# Sensor_Board_2_01_HX711_DS18b2.net
KiCad netlist of a schematic drawn in EAGLE
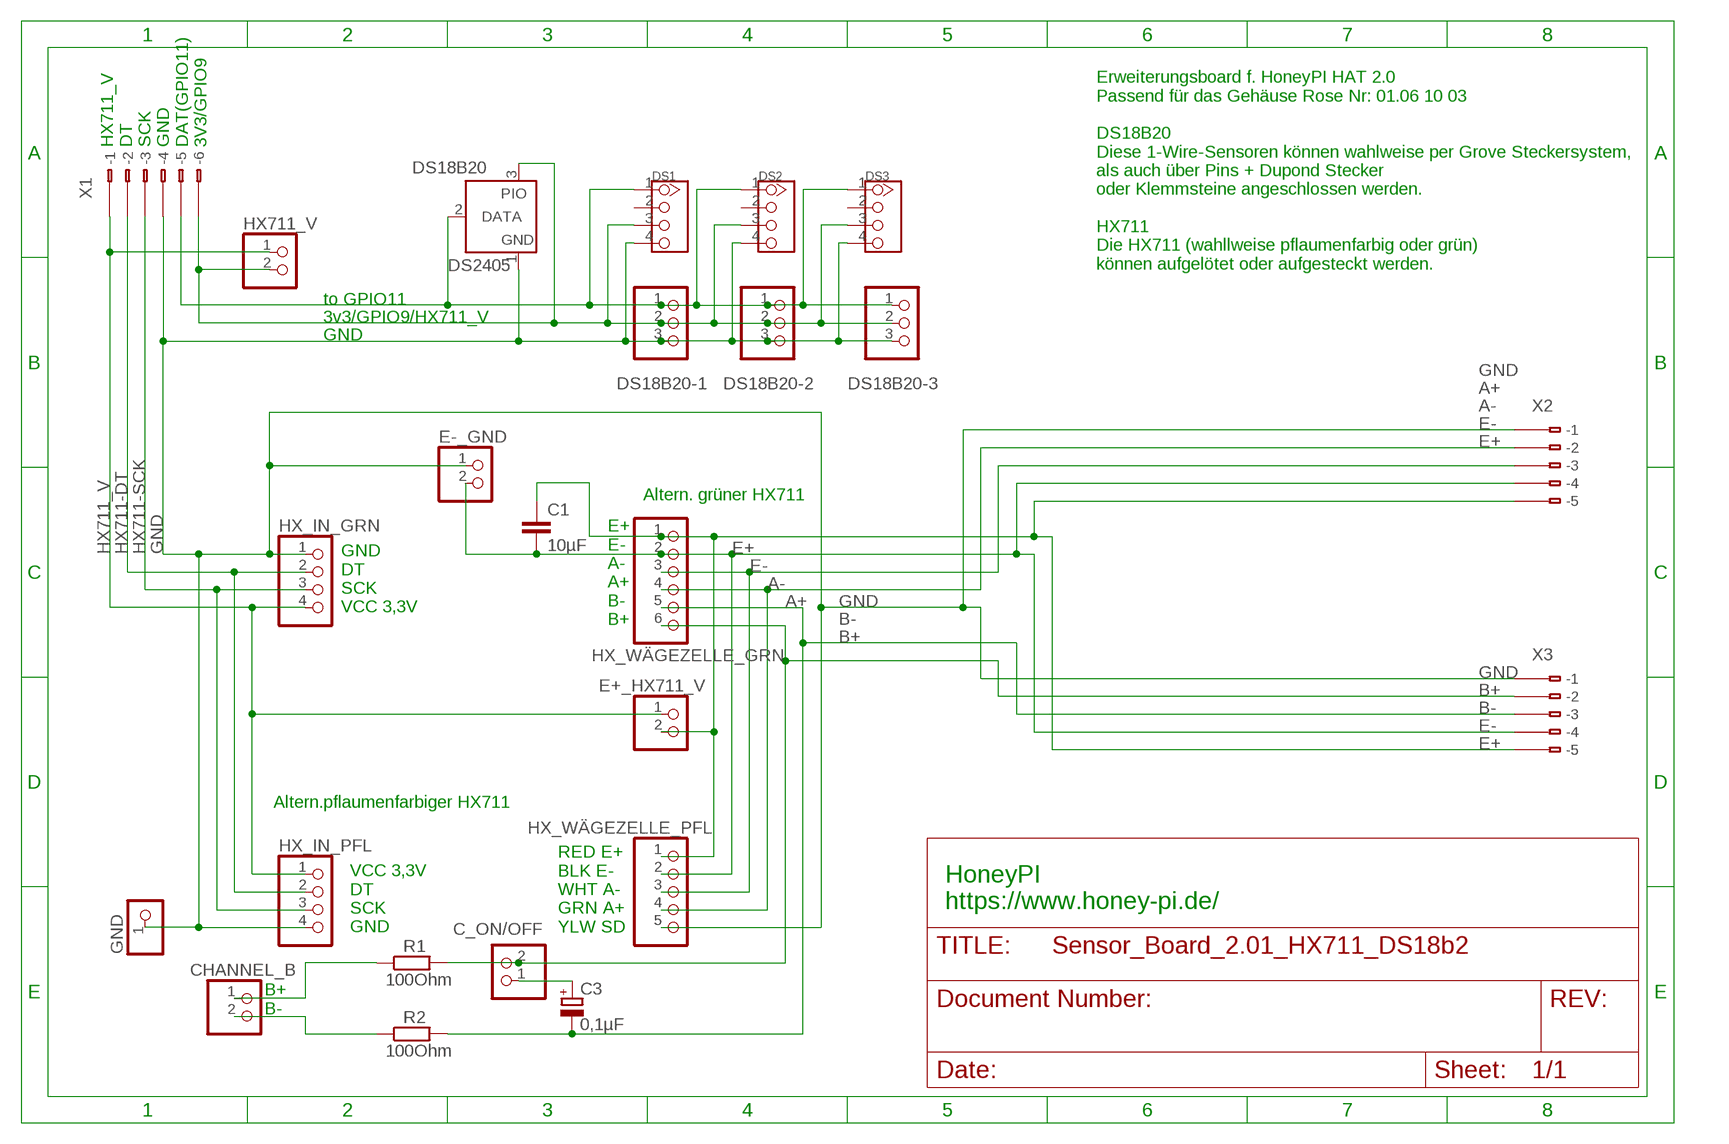
[diagram p0: schematic, sheet 1]

(export (version "E")
  (design (tool "Eeschema 10.0.6"))
  (components
    (comp (ref "C1")
      (value "10µF")
      (footprint "eagle-import:C5B2.5")
      (libsource (lib "eagle-import") (part "C5/2.5"))
    )
    (comp (ref "C3")
      (value "0,1µF")
      (footprint "eagle-import:E2,5-7")
      (libsource (lib "eagle-import") (part "CPOL-EUE2.5-7"))
    )
    (comp (ref "CHANNEL_B")
      (value "PINHD-1X2")
      (footprint "eagle-import:1X02")
      (libsource (lib "eagle-import") (part "PINHD-1X2"))
    )
    (comp (ref "C_ON/OFF")
      (value "PINHD-1X2")
      (footprint "eagle-import:1X02")
      (libsource (lib "eagle-import") (part "PINHD-1X2"))
    )
    (comp (ref "DS1")
      (value "TWIG-4P-2.0-2.0")
      (footprint "eagle-import:4P-2.0")
      (libsource (lib "eagle-import") (part "TWIG-4P-2.0-2.0"))
    )
    (comp (ref "DS2")
      (value "TWIG-4P-2.0-2.0")
      (footprint "eagle-import:4P-2.0")
      (libsource (lib "eagle-import") (part "TWIG-4P-2.0-2.0"))
    )
    (comp (ref "DS3")
      (value "TWIG-4P-2.0-2.0")
      (footprint "eagle-import:4P-2.0")
      (libsource (lib "eagle-import") (part "TWIG-4P-2.0-2.0"))
    )
    (comp (ref "DS18B20")
      (value "DS2405")
      (footprint "eagle-import:TO92-")
      (fields (field (name "MF") "DALLAS SEMICONDUCTOR"))
      (libsource (lib "eagle-import") (part "DS2405"))
    )
    (comp (ref "DS18B20-1")
      (value "PINHD-1X3")
      (footprint "eagle-import:1X03")
      (libsource (lib "eagle-import") (part "PINHD-1X3"))
    )
    (comp (ref "DS18B20-2")
      (value "PINHD-1X3")
      (footprint "eagle-import:1X03")
      (libsource (lib "eagle-import") (part "PINHD-1X3"))
    )
    (comp (ref "DS18B20-3")
      (value "PINHD-1X3")
      (footprint "eagle-import:1X03")
      (libsource (lib "eagle-import") (part "PINHD-1X3"))
    )
    (comp (ref "E+_HX711_V")
      (value "PINHD-1X2")
      (footprint "eagle-import:1X02")
      (libsource (lib "eagle-import") (part "PINHD-1X2"))
    )
    (comp (ref "E-_GND")
      (value "PINHD-1X2")
      (footprint "eagle-import:1X02")
      (libsource (lib "eagle-import") (part "PINHD-1X2"))
    )
    (comp (ref "GND")
      (value "PINHD-1X1")
      (footprint "eagle-import:1X01")
      (libsource (lib "eagle-import") (part "PINHD-1X1"))
    )
    (comp (ref "HX711_V")
      (value "PINHD-1X2")
      (footprint "eagle-import:1X02")
      (libsource (lib "eagle-import") (part "PINHD-1X2"))
    )
    (comp (ref "HX_IN_GRN")
      (value "PINHD-1X4")
      (footprint "eagle-import:1X04")
      (libsource (lib "eagle-import") (part "PINHD-1X4"))
    )
    (comp (ref "HX_IN_PFL")
      (value "PINHD-1X4")
      (footprint "eagle-import:1X04")
      (libsource (lib "eagle-import") (part "PINHD-1X4"))
    )
    (comp (ref "HX_WÄGEZELLE_GRN")
      (value "PINHD-1X6")
      (footprint "eagle-import:1X06")
      (libsource (lib "eagle-import") (part "PINHD-1X6"))
    )
    (comp (ref "HX_WÄGEZELLE_PFL")
      (value "PINHD-1X5")
      (footprint "eagle-import:1X05")
      (libsource (lib "eagle-import") (part "PINHD-1X5"))
    )
    (comp (ref "R1")
      (value "100Ohm")
      (footprint "eagle-import:0207_10")
      (libsource (lib "eagle-import") (part "R-EU_0207/10"))
    )
    (comp (ref "R2")
      (value "100Ohm")
      (footprint "eagle-import:0207_10")
      (libsource (lib "eagle-import") (part "R-EU_0207/10"))
    )
    (comp (ref "X1")
      (value "233-506")
      (footprint "eagle-import:233-506")
      (fields (field (name "MF") "Wago Corporation") (field (name "MPN") "0233-0506"))
      (libsource (lib "eagle-import") (part "233-506"))
    )
    (comp (ref "X2")
      (value "233-505")
      (footprint "eagle-import:233-505")
      (fields (field (name "MF") "Wago Corporation") (field (name "MPN") "0233-0505"))
      (libsource (lib "eagle-import") (part "233-505"))
    )
    (comp (ref "X3")
      (value "233-505")
      (footprint "eagle-import:233-505")
      (fields (field (name "MF") "Wago Corporation") (field (name "MPN") "0233-0505"))
      (libsource (lib "eagle-import") (part "233-505"))
    )
  )
  (nets
    (net (code "1") (name "/A+") (class "Default")
      (node (ref "HX_WÄGEZELLE_GRN") (pin "4") (pinfunction "4_4") (pintype "passive"))
      (node (ref "HX_WÄGEZELLE_PFL") (pin "4") (pinfunction "4_4") (pintype "passive"))
      (node (ref "X2") (pin "B2") (pinfunction "B-2_B2") (pintype "passive"))
    )
    (net (code "2") (name "/A-") (class "Default")
      (node (ref "HX_WÄGEZELLE_GRN") (pin "3") (pinfunction "3_3") (pintype "passive"))
      (node (ref "HX_WÄGEZELLE_PFL") (pin "3") (pinfunction "3_3") (pintype "passive"))
      (node (ref "X2") (pin "B3") (pinfunction "B-3_B3") (pintype "passive"))
    )
    (net (code "3") (name "/B+") (class "Default")
      (node (ref "C_ON/OFF") (pin "2") (pinfunction "2_2") (pintype "passive"))
      (node (ref "HX_WÄGEZELLE_GRN") (pin "6") (pinfunction "6_6") (pintype "passive"))
      (node (ref "R1") (pin "2") (pinfunction "2_2") (pintype "passive"))
      (node (ref "X3") (pin "B2") (pinfunction "B-2_B2") (pintype "passive"))
    )
    (net (code "4") (name "/B-") (class "Default")
      (node (ref "C3") (pin "-") (pinfunction "-_-") (pintype "passive"))
      (node (ref "HX_WÄGEZELLE_GRN") (pin "5") (pinfunction "5_5") (pintype "passive"))
      (node (ref "R2") (pin "2") (pinfunction "2_2") (pintype "passive"))
      (node (ref "X3") (pin "B3") (pinfunction "B-3_B3") (pintype "passive"))
    )
    (net (code "5") (name "/E+") (class "Default")
      (node (ref "C1") (pin "1") (pinfunction "1_1") (pintype "passive"))
      (node (ref "E+_HX711_V") (pin "2") (pinfunction "2_2") (pintype "passive"))
      (node (ref "HX_WÄGEZELLE_GRN") (pin "1") (pinfunction "1_1") (pintype "passive"))
      (node (ref "HX_WÄGEZELLE_PFL") (pin "1") (pinfunction "1_1") (pintype "passive"))
      (node (ref "X2") (pin "B5") (pinfunction "B-5_B5") (pintype "passive"))
      (node (ref "X3") (pin "B5") (pinfunction "B-5_B5") (pintype "passive"))
    )
    (net (code "6") (name "/E-") (class "Default")
      (node (ref "C1") (pin "2") (pinfunction "2_2") (pintype "passive"))
      (node (ref "E-_GND") (pin "2") (pinfunction "2_2") (pintype "passive"))
      (node (ref "HX_WÄGEZELLE_GRN") (pin "2") (pinfunction "2_2") (pintype "passive"))
      (node (ref "HX_WÄGEZELLE_PFL") (pin "2") (pinfunction "2_2") (pintype "passive"))
      (node (ref "X2") (pin "B4") (pinfunction "B-4_B4") (pintype "passive"))
      (node (ref "X3") (pin "B4") (pinfunction "B-4_B4") (pintype "passive"))
    )
    (net (code "7") (name "/GND") (class "Default")
      (node (ref "DS1") (pin "4") (pinfunction "4_4") (pintype "bidirectional"))
      (node (ref "DS18B20") (pin "1") (pinfunction "GND_1") (pintype "passive"))
      (node (ref "DS18B20-1") (pin "3") (pinfunction "3_3") (pintype "passive"))
      (node (ref "DS18B20-2") (pin "3") (pinfunction "3_3") (pintype "passive"))
      (node (ref "DS18B20-3") (pin "3") (pinfunction "3_3") (pintype "passive"))
      (node (ref "DS2") (pin "4") (pinfunction "4_4") (pintype "bidirectional"))
      (node (ref "DS3") (pin "4") (pinfunction "4_4") (pintype "bidirectional"))
      (node (ref "E-_GND") (pin "1") (pinfunction "1_1") (pintype "passive"))
      (node (ref "GND") (pin "1") (pinfunction "1_1") (pintype "passive"))
      (node (ref "HX_IN_GRN") (pin "1") (pinfunction "1_1") (pintype "passive"))
      (node (ref "HX_IN_PFL") (pin "4") (pinfunction "4_4") (pintype "passive"))
      (node (ref "HX_WÄGEZELLE_PFL") (pin "5") (pinfunction "5_5") (pintype "passive"))
      (node (ref "X1") (pin "B4") (pinfunction "B-4_B4") (pintype "passive"))
      (node (ref "X2") (pin "B1") (pinfunction "B-1_B1") (pintype "passive"))
      (node (ref "X3") (pin "B1") (pinfunction "B-1_B1") (pintype "passive"))
    )
    (net (code "8") (name "/HX711-DT") (class "Default")
      (node (ref "HX_IN_GRN") (pin "2") (pinfunction "2_2") (pintype "passive"))
      (node (ref "HX_IN_PFL") (pin "2") (pinfunction "2_2") (pintype "passive"))
      (node (ref "X1") (pin "B2") (pinfunction "B-2_B2") (pintype "passive"))
    )
    (net (code "9") (name "/HX711-SCK") (class "Default")
      (node (ref "HX_IN_GRN") (pin "3") (pinfunction "3_3") (pintype "passive"))
      (node (ref "HX_IN_PFL") (pin "3") (pinfunction "3_3") (pintype "passive"))
      (node (ref "X1") (pin "B3") (pinfunction "B-3_B3") (pintype "passive"))
    )
    (net (code "10") (name "/HX711_V") (class "Default")
      (node (ref "E+_HX711_V") (pin "1") (pinfunction "1_1") (pintype "passive"))
      (node (ref "HX711_V") (pin "1") (pinfunction "1_1") (pintype "passive"))
      (node (ref "HX_IN_GRN") (pin "4") (pinfunction "4_4") (pintype "passive"))
      (node (ref "HX_IN_PFL") (pin "1") (pinfunction "1_1") (pintype "passive"))
      (node (ref "X1") (pin "B1") (pinfunction "B-1_B1") (pintype "passive"))
    )
    (net (code "11") (name "Net-(C3-Pad+)") (class "Default")
      (node (ref "C3") (pin "+") (pinfunction "+_+") (pintype "passive"))
      (node (ref "C_ON/OFF") (pin "1") (pinfunction "1_1") (pintype "passive"))
    )
    (net (code "12") (name "Net-(CHANNEL_B-Pad1)") (class "Default")
      (node (ref "CHANNEL_B") (pin "1") (pinfunction "1_1") (pintype "passive"))
      (node (ref "R1") (pin "1") (pinfunction "1_1") (pintype "passive"))
    )
    (net (code "13") (name "Net-(CHANNEL_B-Pad2)") (class "Default")
      (node (ref "CHANNEL_B") (pin "2") (pinfunction "2_2") (pintype "passive"))
      (node (ref "R2") (pin "1") (pinfunction "1_1") (pintype "passive"))
    )
    (net (code "14") (name "Net-(DS18B20-DATA)") (class "Default")
      (node (ref "DS1") (pin "1") (pinfunction "1_1") (pintype "bidirectional"))
      (node (ref "DS18B20") (pin "2") (pinfunction "DATA_2") (pintype "input"))
      (node (ref "DS18B20-1") (pin "1") (pinfunction "1_1") (pintype "passive"))
      (node (ref "DS18B20-2") (pin "1") (pinfunction "1_1") (pintype "passive"))
      (node (ref "DS18B20-3") (pin "1") (pinfunction "1_1") (pintype "passive"))
      (node (ref "DS2") (pin "1") (pinfunction "1_1") (pintype "bidirectional"))
      (node (ref "DS3") (pin "1") (pinfunction "1_1") (pintype "bidirectional"))
      (node (ref "X1") (pin "B5") (pinfunction "B-5_B5") (pintype "passive"))
    )
    (net (code "15") (name "Net-(DS18B20-PIO)") (class "Default")
      (node (ref "DS1") (pin "3") (pinfunction "3_3") (pintype "bidirectional"))
      (node (ref "DS18B20") (pin "3") (pinfunction "PIO_3") (pintype "passive"))
      (node (ref "DS18B20-1") (pin "2") (pinfunction "2_2") (pintype "passive"))
      (node (ref "DS18B20-2") (pin "2") (pinfunction "2_2") (pintype "passive"))
      (node (ref "DS18B20-3") (pin "2") (pinfunction "2_2") (pintype "passive"))
      (node (ref "DS2") (pin "3") (pinfunction "3_3") (pintype "bidirectional"))
      (node (ref "DS3") (pin "3") (pinfunction "3_3") (pintype "bidirectional"))
      (node (ref "HX711_V") (pin "2") (pinfunction "2_2") (pintype "passive"))
      (node (ref "X1") (pin "B6") (pinfunction "B-6_B6") (pintype "passive"))
    )
    (net (code "16") (name "unconnected-(DS1-Pad2)") (class "Default")
      (node (ref "DS1") (pin "2") (pinfunction "2_2") (pintype "bidirectional"))
    )
    (net (code "17") (name "unconnected-(DS2-Pad2)") (class "Default")
      (node (ref "DS2") (pin "2") (pinfunction "2_2") (pintype "bidirectional"))
    )
    (net (code "18") (name "unconnected-(DS3-Pad2)") (class "Default")
      (node (ref "DS3") (pin "2") (pinfunction "2_2") (pintype "bidirectional"))
    )
    (net (code "19") (name "unconnected-(X1--1-PadA1)") (class "Default")
      (node (ref "X1") (pin "A1") (pinfunction "-1_A1") (pintype "passive"))
    )
    (net (code "20") (name "unconnected-(X1--2-PadA2)") (class "Default")
      (node (ref "X1") (pin "A2") (pinfunction "-2_A2") (pintype "passive"))
    )
    (net (code "21") (name "unconnected-(X1--3-PadA3)") (class "Default")
      (node (ref "X1") (pin "A3") (pinfunction "-3_A3") (pintype "passive"))
    )
    (net (code "22") (name "unconnected-(X1--4-PadA4)") (class "Default")
      (node (ref "X1") (pin "A4") (pinfunction "-4_A4") (pintype "passive"))
    )
    (net (code "23") (name "unconnected-(X1--5-PadA5)") (class "Default")
      (node (ref "X1") (pin "A5") (pinfunction "-5_A5") (pintype "passive"))
    )
    (net (code "24") (name "unconnected-(X1--6-PadA6)") (class "Default")
      (node (ref "X1") (pin "A6") (pinfunction "-6_A6") (pintype "passive"))
    )
    (net (code "25") (name "unconnected-(X2--1-PadA1)") (class "Default")
      (node (ref "X2") (pin "A1") (pinfunction "-1_A1") (pintype "passive"))
    )
    (net (code "26") (name "unconnected-(X2--2-PadA2)") (class "Default")
      (node (ref "X2") (pin "A2") (pinfunction "-2_A2") (pintype "passive"))
    )
    (net (code "27") (name "unconnected-(X2--3-PadA3)") (class "Default")
      (node (ref "X2") (pin "A3") (pinfunction "-3_A3") (pintype "passive"))
    )
    (net (code "28") (name "unconnected-(X2--4-PadA4)") (class "Default")
      (node (ref "X2") (pin "A4") (pinfunction "-4_A4") (pintype "passive"))
    )
    (net (code "29") (name "unconnected-(X2--5-PadA5)") (class "Default")
      (node (ref "X2") (pin "A5") (pinfunction "-5_A5") (pintype "passive"))
    )
    (net (code "30") (name "unconnected-(X3--1-PadA1)") (class "Default")
      (node (ref "X3") (pin "A1") (pinfunction "-1_A1") (pintype "passive"))
    )
    (net (code "31") (name "unconnected-(X3--2-PadA2)") (class "Default")
      (node (ref "X3") (pin "A2") (pinfunction "-2_A2") (pintype "passive"))
    )
    (net (code "32") (name "unconnected-(X3--3-PadA3)") (class "Default")
      (node (ref "X3") (pin "A3") (pinfunction "-3_A3") (pintype "passive"))
    )
    (net (code "33") (name "unconnected-(X3--4-PadA4)") (class "Default")
      (node (ref "X3") (pin "A4") (pinfunction "-4_A4") (pintype "passive"))
    )
    (net (code "34") (name "unconnected-(X3--5-PadA5)") (class "Default")
      (node (ref "X3") (pin "A5") (pinfunction "-5_A5") (pintype "passive"))
    )
  )
)
